# CPU.net
KiCad netlist of a schematic drawn in Altium Designer
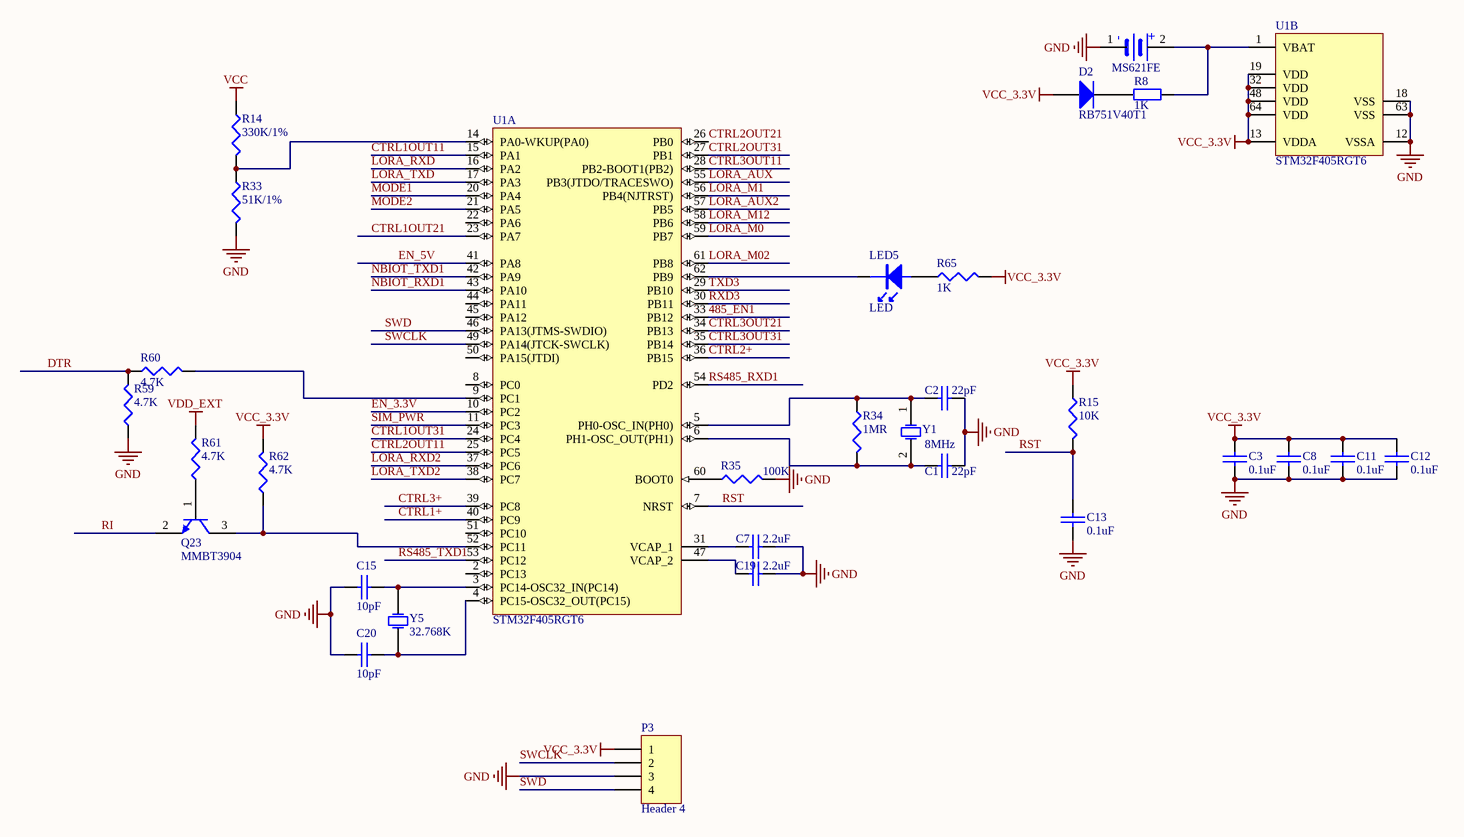
[diagram p0: CPU.SchDoc]

(export (version "E")
  (design (tool "Eeschema 10.0.6"))
  (components
    (comp (ref "C1")
      (value "22pF")
      (footprint "0603c")
      (description "Capacitor")
      (libsource (lib "SM") (part "CAP"))
    )
    (comp (ref "C2")
      (value "22pF")
      (footprint "0603c")
      (description "Capacitor")
      (libsource (lib "SM") (part "CAP"))
    )
    (comp (ref "C3")
      (value "0.1uF")
      (footprint "0603c")
      (description "Capacitor")
      (libsource (lib "SM") (part "CAP"))
    )
    (comp (ref "C7")
      (value "2.2uF")
      (footprint "0603c")
      (description "Capacitor")
      (libsource (lib "SM") (part "CAP"))
    )
    (comp (ref "C8")
      (value "0.1uF")
      (footprint "0603c")
      (description "Capacitor")
      (libsource (lib "SM") (part "CAP"))
    )
    (comp (ref "C11")
      (value "0.1uF")
      (footprint "0603c")
      (description "Capacitor")
      (libsource (lib "SM") (part "CAP"))
    )
    (comp (ref "C12")
      (value "0.1uF")
      (footprint "0603c")
      (description "Capacitor")
      (libsource (lib "SM") (part "CAP"))
    )
    (comp (ref "C13")
      (value "0.1uF")
      (footprint "0603c")
      (description "Capacitor")
      (libsource (lib "SM") (part "CAP"))
    )
    (comp (ref "C15")
      (value "10pF")
      (footprint "0603c")
      (description "Capacitor")
      (libsource (lib "SM") (part "CAP"))
    )
    (comp (ref "C19")
      (value "2.2uF")
      (footprint "0603c")
      (description "Capacitor")
      (libsource (lib "SM") (part "CAP"))
    )
    (comp (ref "C20")
      (value "10pF")
      (footprint "0603c")
      (description "Capacitor")
      (libsource (lib "SM") (part "CAP"))
    )
    (comp (ref "D2")
      (value "RB751V40T1")
      (footprint "SOD323")
      (description "Default Diode")
      (fields (field (name "PUBLISHER") "Altium Limited"))
      (libsource (lib "Miscellaneous Devices") (part "Diode"))
    )
    (comp (ref "LED5") (value "LED") (footprint "0603LED") (libsource (lib "我的元件库") (part "LED")))
    (comp (ref "MS621FE")
      (value "SBatery")
      (footprint "MS621FE")
      (libsource (lib "Myself_1") (part "SBatery"))
    )
    (comp (ref "P3")
      (value "Header 4")
      (footprint "HDR1X4")
      (description "Header, 4-Pin")
      (fields (field (name "PUBLISHER") "Altium Limited"))
      (libsource (lib "Miscellaneous Connectors") (part "Header 4"))
    )
    (comp (ref "Q23") (value "MMBT3904") (footprint "SOT23-3") (libsource (lib "Schlib1") (part "NPN")))
    (comp (ref "R8")
      (value "1K")
      (footprint "0603R")
      (description "Resistor")
      (fields (field (name "PUBLISHER") "Altium Limited"))
      (libsource (lib "Miscellaneous Devices") (part "Res2"))
    )
    (comp (ref "R14")
      (value "330K/1%")
      (footprint "0603R")
      (description "Resistor")
      (fields (field (name "PUBLISHER") "Altium Limited"))
      (libsource (lib "SM") (part "Res3"))
    )
    (comp (ref "R15")
      (value "10K")
      (footprint "0603R")
      (description "Resistor")
      (fields (field (name "PUBLISHER") "Altium Limited"))
      (libsource (lib "SM") (part "Res3"))
    )
    (comp (ref "R33")
      (value "51K/1%")
      (footprint "0603R")
      (description "Resistor")
      (fields (field (name "PUBLISHER") "Altium Limited"))
      (libsource (lib "SM") (part "Res3"))
    )
    (comp (ref "R34")
      (value "1MR")
      (footprint "0603R")
      (description "Resistor")
      (fields (field (name "PUBLISHER") "Altium Limited"))
      (libsource (lib "SM") (part "Res3"))
    )
    (comp (ref "R35")
      (value "100K")
      (footprint "0603R")
      (description "Resistor")
      (fields (field (name "PUBLISHER") "Altium Limited"))
      (libsource (lib "SM") (part "Res3"))
    )
    (comp (ref "R59")
      (value "4.7K")
      (footprint "0603R")
      (libsource (lib "ZWLIntegrated_Library") (part "RES1"))
    )
    (comp (ref "R60")
      (value "4.7K")
      (footprint "0603R")
      (libsource (lib "ZWLIntegrated_Library") (part "RES1"))
    )
    (comp (ref "R61")
      (value "4.7K")
      (footprint "0603R")
      (libsource (lib "ZWLIntegrated_Library") (part "RES1"))
    )
    (comp (ref "R62")
      (value "4.7K")
      (footprint "0603R")
      (libsource (lib "ZWLIntegrated_Library") (part "RES1"))
    )
    (comp (ref "R65")
      (value "1K")
      (footprint "0603R")
      (libsource (lib "ZWLIntegrated_Library") (part "RES1"))
    )
    (comp (ref "U1")
      (value "STM32F405RGT6")
      (footprint "LQFP-64")
      (fields (field (name "MANUFACTURER") "STMicroelectronics"))
      (libsource (lib "STMicroelectronics STM32 F4") (part "STM32F405RGT6"))
    )
    (comp (ref "Y1")
      (value "8MHz")
      (footprint "CRAY_5032")
      (description "Crystal Oscillator")
      (fields (field (name "PUBLISHER") "Altium Limited"))
      (libsource (lib "Miscellaneous Devices") (part "XTAL"))
    )
    (comp (ref "Y5")
      (value "32.768K")
      (footprint "32.768K")
      (description "Crystal Oscillator")
      (fields (field (name "PUBLISHER") "Altium Limited"))
      (libsource (lib "") (part "XTAL_1"))
    )
  )
  (nets
    (net (code "1") (name "/485_EN1") (class "Default")
      (node (ref "U1") (pin "33") (pinfunction "PB12_33") (pintype "bidirectional"))
    )
    (net (code "2") (name "/CTRL1+") (class "Default")
      (node (ref "U1") (pin "40") (pinfunction "PC9_40") (pintype "bidirectional"))
    )
    (net (code "3") (name "/CTRL1OUT11") (class "Default")
      (node (ref "U1") (pin "15") (pinfunction "PA1_15") (pintype "bidirectional"))
    )
    (net (code "4") (name "/CTRL1OUT21") (class "Default")
      (node (ref "U1") (pin "23") (pinfunction "PA7_23") (pintype "bidirectional"))
    )
    (net (code "5") (name "/CTRL1OUT31") (class "Default")
      (node (ref "U1") (pin "24") (pinfunction "PC4_24") (pintype "bidirectional"))
    )
    (net (code "6") (name "/CTRL2+") (class "Default")
      (node (ref "U1") (pin "36") (pinfunction "PB15_36") (pintype "bidirectional"))
    )
    (net (code "7") (name "/CTRL2OUT11") (class "Default")
      (node (ref "U1") (pin "25") (pinfunction "PC5_25") (pintype "bidirectional"))
    )
    (net (code "8") (name "/CTRL2OUT21") (class "Default")
      (node (ref "U1") (pin "26") (pinfunction "PB0_26") (pintype "bidirectional"))
    )
    (net (code "9") (name "/CTRL2OUT31") (class "Default")
      (node (ref "U1") (pin "27") (pinfunction "PB1_27") (pintype "bidirectional"))
    )
    (net (code "10") (name "/CTRL3+") (class "Default")
      (node (ref "U1") (pin "39") (pinfunction "PC8_39") (pintype "bidirectional"))
    )
    (net (code "11") (name "/CTRL3OUT11") (class "Default")
      (node (ref "U1") (pin "28") (pinfunction "PB2-BOOT1(PB2)_28") (pintype "bidirectional"))
    )
    (net (code "12") (name "/CTRL3OUT21") (class "Default")
      (node (ref "U1") (pin "34") (pinfunction "PB13_34") (pintype "bidirectional"))
    )
    (net (code "13") (name "/CTRL3OUT31") (class "Default")
      (node (ref "U1") (pin "35") (pinfunction "PB14_35") (pintype "bidirectional"))
    )
    (net (code "14") (name "/DTR") (class "Default")
      (node (ref "R59") (pin "2") (pinfunction "2_2") (pintype "passive"))
      (node (ref "R60") (pin "1") (pinfunction "1_1") (pintype "passive"))
    )
    (net (code "15") (name "/EN_3.3V") (class "Default")
      (node (ref "U1") (pin "10") (pinfunction "PC2_10") (pintype "bidirectional"))
    )
    (net (code "16") (name "/EN_5V") (class "Default")
      (node (ref "U1") (pin "41") (pinfunction "PA8_41") (pintype "bidirectional"))
    )
    (net (code "17") (name "/LORA_AUX") (class "Default")
      (node (ref "U1") (pin "55") (pinfunction "PB3(JTDO/TRACESWO)_55") (pintype "bidirectional"))
    )
    (net (code "18") (name "/LORA_AUX2") (class "Default")
      (node (ref "U1") (pin "57") (pinfunction "PB5_57") (pintype "bidirectional"))
    )
    (net (code "19") (name "/LORA_M0") (class "Default")
      (node (ref "U1") (pin "59") (pinfunction "PB7_59") (pintype "bidirectional"))
    )
    (net (code "20") (name "/LORA_M1") (class "Default")
      (node (ref "U1") (pin "56") (pinfunction "PB4(NJTRST)_56") (pintype "bidirectional"))
    )
    (net (code "21") (name "/LORA_M02") (class "Default")
      (node (ref "U1") (pin "61") (pinfunction "PB8_61") (pintype "bidirectional"))
    )
    (net (code "22") (name "/LORA_M12") (class "Default")
      (node (ref "U1") (pin "58") (pinfunction "PB6_58") (pintype "bidirectional"))
    )
    (net (code "23") (name "/LORA_RXD") (class "Default")
      (node (ref "U1") (pin "16") (pinfunction "PA2_16") (pintype "bidirectional"))
    )
    (net (code "24") (name "/LORA_RXD2") (class "Default")
      (node (ref "U1") (pin "37") (pinfunction "PC6_37") (pintype "bidirectional"))
    )
    (net (code "25") (name "/LORA_TXD") (class "Default")
      (node (ref "U1") (pin "17") (pinfunction "PA3_17") (pintype "bidirectional"))
    )
    (net (code "26") (name "/LORA_TXD2") (class "Default")
      (node (ref "U1") (pin "38") (pinfunction "PC7_38") (pintype "bidirectional"))
    )
    (net (code "27") (name "/MODE1") (class "Default")
      (node (ref "U1") (pin "20") (pinfunction "PA4_20") (pintype "bidirectional"))
    )
    (net (code "28") (name "/MODE2") (class "Default")
      (node (ref "U1") (pin "21") (pinfunction "PA5_21") (pintype "bidirectional"))
    )
    (net (code "29") (name "/NBIOT_RXD1") (class "Default")
      (node (ref "U1") (pin "43") (pinfunction "PA10_43") (pintype "bidirectional"))
    )
    (net (code "30") (name "/NBIOT_TXD1") (class "Default")
      (node (ref "U1") (pin "42") (pinfunction "PA9_42") (pintype "bidirectional"))
    )
    (net (code "31") (name "/RI") (class "Default")
      (node (ref "Q23") (pin "2") (pinfunction "E_2") (pintype "passive"))
    )
    (net (code "32") (name "/RS485_RXD1") (class "Default")
      (node (ref "U1") (pin "54") (pinfunction "PD2_54") (pintype "bidirectional"))
    )
    (net (code "33") (name "/RS485_TXD1") (class "Default")
      (node (ref "U1") (pin "53") (pinfunction "PC12_53") (pintype "bidirectional"))
    )
    (net (code "34") (name "/RST") (class "Default")
      (node (ref "C13") (pin "2") (pinfunction "2_2") (pintype "passive"))
      (node (ref "R15") (pin "2") (pinfunction "2_2") (pintype "passive"))
      (node (ref "U1") (pin "7") (pinfunction "NRST_7") (pintype "bidirectional"))
    )
    (net (code "35") (name "/RXD3") (class "Default")
      (node (ref "U1") (pin "30") (pinfunction "PB11_30") (pintype "bidirectional"))
    )
    (net (code "36") (name "/SIM_PWR") (class "Default")
      (node (ref "U1") (pin "11") (pinfunction "PC3_11") (pintype "bidirectional"))
    )
    (net (code "37") (name "/SWCLK") (class "Default")
      (node (ref "P3") (pin "2") (pinfunction "2_2") (pintype "passive"))
      (node (ref "U1") (pin "49") (pinfunction "PA14(JTCK-SWCLK)_49") (pintype "bidirectional"))
    )
    (net (code "38") (name "/SWD") (class "Default")
      (node (ref "P3") (pin "4") (pinfunction "4_4") (pintype "passive"))
      (node (ref "U1") (pin "46") (pinfunction "PA13(JTMS-SWDIO)_46") (pintype "bidirectional"))
    )
    (net (code "39") (name "/TXD3") (class "Default")
      (node (ref "U1") (pin "29") (pinfunction "PB10_29") (pintype "bidirectional"))
    )
    (net (code "40") (name "GND") (class "Default")
      (node (ref "C1") (pin "1") (pinfunction "1_1") (pintype "passive"))
      (node (ref "C11") (pin "1") (pinfunction "1_1") (pintype "passive"))
      (node (ref "C12") (pin "1") (pinfunction "1_1") (pintype "passive"))
      (node (ref "C13") (pin "1") (pinfunction "1_1") (pintype "passive"))
      (node (ref "C15") (pin "1") (pinfunction "1_1") (pintype "passive"))
      (node (ref "C19") (pin "1") (pinfunction "1_1") (pintype "passive"))
      (node (ref "C2") (pin "1") (pinfunction "1_1") (pintype "passive"))
      (node (ref "C20") (pin "1") (pinfunction "1_1") (pintype "passive"))
      (node (ref "C3") (pin "1") (pinfunction "1_1") (pintype "passive"))
      (node (ref "C7") (pin "1") (pinfunction "1_1") (pintype "passive"))
      (node (ref "C8") (pin "1") (pinfunction "1_1") (pintype "passive"))
      (node (ref "MS621FE") (pin "1") (pinfunction "1_1") (pintype "passive"))
      (node (ref "P3") (pin "3") (pinfunction "3_3") (pintype "passive"))
      (node (ref "R33") (pin "2") (pinfunction "2_2") (pintype "passive"))
      (node (ref "R35") (pin "2") (pinfunction "2_2") (pintype "passive"))
      (node (ref "R59") (pin "1") (pinfunction "1_1") (pintype "passive"))
      (node (ref "U1") (pin "12") (pinfunction "VSSA_12") (pintype "power_in"))
      (node (ref "U1") (pin "18") (pinfunction "VSS_18") (pintype "power_in"))
      (node (ref "U1") (pin "63") (pinfunction "VSS_63") (pintype "power_in"))
    )
    (net (code "41") (name "Net-(D2-K)") (class "Default")
      (node (ref "D2") (pin "2") (pinfunction "K_2") (pintype "passive"))
      (node (ref "R8") (pin "1") (pinfunction "1_1") (pintype "passive"))
    )
    (net (code "42") (name "Net-(LED5-Pad1)") (class "Default")
      (node (ref "LED5") (pin "1") (pinfunction "1_1") (pintype "passive"))
      (node (ref "R65") (pin "1") (pinfunction "1_1") (pintype "passive"))
    )
    (net (code "43") (name "Net-(Q23-B)") (class "Default")
      (node (ref "Q23") (pin "1") (pinfunction "B_1") (pintype "passive"))
      (node (ref "R61") (pin "1") (pinfunction "1_1") (pintype "passive"))
    )
    (net (code "44") (name "Net-(Q23-C)") (class "Default")
      (node (ref "Q23") (pin "3") (pinfunction "C_3") (pintype "passive"))
      (node (ref "R62") (pin "1") (pinfunction "1_1") (pintype "passive"))
      (node (ref "U1") (pin "52") (pinfunction "PC11_52") (pintype "bidirectional"))
    )
    (net (code "45") (name "Net-(U1A-BOOT0)") (class "Default")
      (node (ref "R35") (pin "1") (pinfunction "1_1") (pintype "passive"))
      (node (ref "U1") (pin "60") (pinfunction "BOOT0_60") (pintype "input"))
    )
    (net (code "46") (name "Net-(U1A-PA0-WKUP(PA0))") (class "Default")
      (node (ref "R14") (pin "2") (pinfunction "2_2") (pintype "passive"))
      (node (ref "R33") (pin "1") (pinfunction "1_1") (pintype "passive"))
      (node (ref "U1") (pin "14") (pinfunction "PA0-WKUP(PA0)_14") (pintype "bidirectional"))
    )
    (net (code "47") (name "Net-(U1A-PB9)") (class "Default")
      (node (ref "LED5") (pin "2") (pinfunction "2_2") (pintype "passive"))
      (node (ref "U1") (pin "62") (pinfunction "PB9_62") (pintype "bidirectional"))
    )
    (net (code "48") (name "Net-(U1A-PC1)") (class "Default")
      (node (ref "R60") (pin "2") (pinfunction "2_2") (pintype "passive"))
      (node (ref "U1") (pin "9") (pinfunction "PC1_9") (pintype "bidirectional"))
    )
    (net (code "49") (name "Net-(U1A-PC14-OSC32_IN(PC14))") (class "Default")
      (node (ref "C15") (pin "2") (pinfunction "2_2") (pintype "passive"))
      (node (ref "U1") (pin "3") (pinfunction "PC14-OSC32_IN(PC14)_3") (pintype "bidirectional"))
      (node (ref "Y5") (pin "1") (pinfunction "OSC1_1") (pintype "passive"))
    )
    (net (code "50") (name "Net-(U1A-PC15-OSC32_OUT(PC15))") (class "Default")
      (node (ref "C20") (pin "2") (pinfunction "2_2") (pintype "passive"))
      (node (ref "U1") (pin "4") (pinfunction "PC15-OSC32_OUT(PC15)_4") (pintype "bidirectional"))
      (node (ref "Y5") (pin "2") (pinfunction "OSC2_2") (pintype "passive"))
    )
    (net (code "51") (name "Net-(U1A-PH0-OSC_IN(PH0))") (class "Default")
      (node (ref "C2") (pin "2") (pinfunction "2_2") (pintype "passive"))
      (node (ref "R34") (pin "1") (pinfunction "1_1") (pintype "passive"))
      (node (ref "U1") (pin "5") (pinfunction "PH0-OSC_IN(PH0)_5") (pintype "bidirectional"))
      (node (ref "Y1") (pin "1") (pinfunction "OSC1_1") (pintype "passive"))
    )
    (net (code "52") (name "Net-(U1A-PH1-OSC_OUT(PH1))") (class "Default")
      (node (ref "C1") (pin "2") (pinfunction "2_2") (pintype "passive"))
      (node (ref "R34") (pin "2") (pinfunction "2_2") (pintype "passive"))
      (node (ref "U1") (pin "6") (pinfunction "PH1-OSC_OUT(PH1)_6") (pintype "bidirectional"))
      (node (ref "Y1") (pin "2") (pinfunction "OSC2_2") (pintype "passive"))
    )
    (net (code "53") (name "Net-(U1A-VCAP_1)") (class "Default")
      (node (ref "C7") (pin "2") (pinfunction "2_2") (pintype "passive"))
      (node (ref "U1") (pin "31") (pinfunction "VCAP_1_31") (pintype "power_in"))
    )
    (net (code "54") (name "Net-(U1A-VCAP_2)") (class "Default")
      (node (ref "C19") (pin "2") (pinfunction "2_2") (pintype "passive"))
      (node (ref "U1") (pin "47") (pinfunction "VCAP_2_47") (pintype "power_in"))
    )
    (net (code "55") (name "Net-(U1B-VBAT)") (class "Default")
      (node (ref "MS621FE") (pin "2") (pinfunction "2_2") (pintype "passive"))
      (node (ref "R8") (pin "2") (pinfunction "2_2") (pintype "passive"))
      (node (ref "U1") (pin "1") (pinfunction "VBAT_1") (pintype "power_in"))
    )
    (net (code "56") (name "VCC") (class "Default")
      (node (ref "R14") (pin "1") (pinfunction "1_1") (pintype "passive"))
    )
    (net (code "57") (name "VCC_3.3V") (class "Default")
      (node (ref "C11") (pin "2") (pinfunction "2_2") (pintype "passive"))
      (node (ref "C12") (pin "2") (pinfunction "2_2") (pintype "passive"))
      (node (ref "C3") (pin "2") (pinfunction "2_2") (pintype "passive"))
      (node (ref "C8") (pin "2") (pinfunction "2_2") (pintype "passive"))
      (node (ref "D2") (pin "1") (pinfunction "A_1") (pintype "passive"))
      (node (ref "P3") (pin "1") (pinfunction "1_1") (pintype "passive"))
      (node (ref "R15") (pin "1") (pinfunction "1_1") (pintype "passive"))
      (node (ref "R62") (pin "2") (pinfunction "2_2") (pintype "passive"))
      (node (ref "R65") (pin "2") (pinfunction "2_2") (pintype "passive"))
      (node (ref "U1") (pin "13") (pinfunction "VDDA_13") (pintype "power_in"))
      (node (ref "U1") (pin "19") (pinfunction "VDD_19") (pintype "power_in"))
      (node (ref "U1") (pin "32") (pinfunction "VDD_32") (pintype "power_in"))
      (node (ref "U1") (pin "48") (pinfunction "VDD_48") (pintype "power_in"))
      (node (ref "U1") (pin "64") (pinfunction "VDD_64") (pintype "power_in"))
    )
    (net (code "58") (name "VDD_EXT") (class "Default")
      (node (ref "R61") (pin "2") (pinfunction "2_2") (pintype "passive"))
    )
    (net (code "59") (name "unconnected-(U1A-PA6-Pad22)") (class "Default")
      (node (ref "U1") (pin "22") (pinfunction "PA6_22") (pintype "bidirectional"))
    )
    (net (code "60") (name "unconnected-(U1A-PA11-Pad44)") (class "Default")
      (node (ref "U1") (pin "44") (pinfunction "PA11_44") (pintype "bidirectional"))
    )
    (net (code "61") (name "unconnected-(U1A-PA12-Pad45)") (class "Default")
      (node (ref "U1") (pin "45") (pinfunction "PA12_45") (pintype "bidirectional"))
    )
    (net (code "62") (name "unconnected-(U1A-PA15(JTDI)-Pad50)") (class "Default")
      (node (ref "U1") (pin "50") (pinfunction "PA15(JTDI)_50") (pintype "bidirectional"))
    )
    (net (code "63") (name "unconnected-(U1A-PC0-Pad8)") (class "Default")
      (node (ref "U1") (pin "8") (pinfunction "PC0_8") (pintype "bidirectional"))
    )
    (net (code "64") (name "unconnected-(U1A-PC10-Pad51)") (class "Default")
      (node (ref "U1") (pin "51") (pinfunction "PC10_51") (pintype "bidirectional"))
    )
    (net (code "65") (name "unconnected-(U1A-PC13-Pad2)") (class "Default")
      (node (ref "U1") (pin "2") (pinfunction "PC13_2") (pintype "bidirectional"))
    )
  )
)
